# AIWAC-TF_CARD-V02.net
KiCad netlist of a schematic drawn in Altium Designer
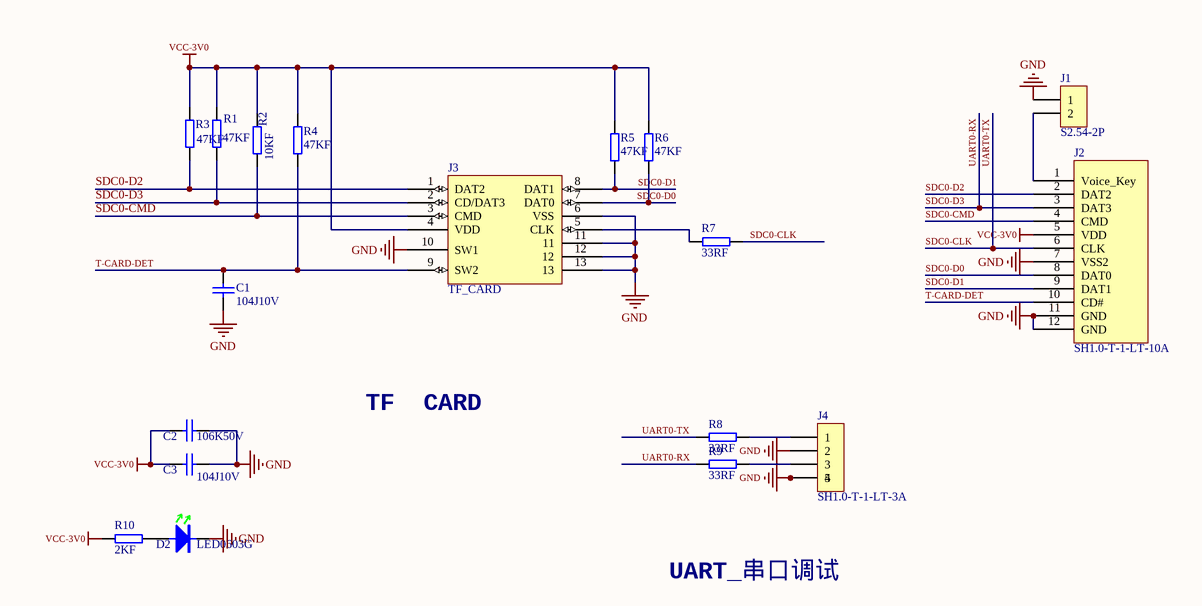
[diagram p0: AIWAC-TF_CARD-V02.SchDoc]

(export (version "E")
  (design (tool "Eeschema 10.0.6"))
  (components
    (comp (ref "C1")
      (value "104J10V")
      (footprint "C0402")
      (description "贴片电容-陶瓷")
      (libsource (lib "Capacitor") (part "C0402X7R-104J10V"))
    )
    (comp (ref "C2")
      (value "106K50V")
      (footprint "C0603")
      (description "贴片电容-陶瓷")
      (libsource (lib "Capacitor") (part "C0603X7R-106K50V"))
    )
    (comp (ref "C3")
      (value "104J10V")
      (footprint "C0402")
      (description "贴片电容-陶瓷")
      (libsource (lib "Capacitor") (part "C0402X7R-104J10V"))
    )
    (comp (ref "D2")
      (value "LED0603G")
      (footprint "D-LED0603G")
      (description "贴片二极管-LED")
      (libsource (lib "Diode") (part "DLED-0603-G"))
    )
    (comp (ref "J1")
      (value "S2.54-2P")
      (footprint "S2.54-2P")
      (description "单排排针-直针")
      (libsource (lib "Connector") (part "J-S2.54-2P"))
    )
    (comp (ref "J2")
      (value "SH1.0-T-1-LT-10A")
      (footprint "J-SH1.0-T-1-LT-10A")
      (description "接插件SH1.0-T-1-LT-10A")
      (libsource (lib "Connector") (part "SH1.0-T-1-LT-10A"))
    )
    (comp (ref "J3")
      (value "TF_CARD")
      (footprint "SD_CARD_7")
      (description "MS110-C10B-C16")
      (libsource (lib "Connector") (part "TF_CARD"))
    )
    (comp (ref "J4")
      (value "SH1.0-T-1-LT-3A")
      (footprint "J-SH1.0-T-1-LT-3A")
      (description "接插件-SH1.0-T-1-LT-3A")
      (libsource (lib "Connector") (part "SH1.0-T-1-LT-3A"))
    )
    (comp (ref "R1")
      (value "47KF")
      (footprint "R0603")
      (description "贴片电阻-通用")
      (libsource (lib "Resistor") (part "R0603-47KF"))
    )
    (comp (ref "R2")
      (value "10KF")
      (footprint "R0603")
      (description "贴片电阻-通用")
      (libsource (lib "Resistor") (part "R0603-10KF"))
    )
    (comp (ref "R3")
      (value "47KF")
      (footprint "R0603")
      (description "贴片电阻-通用")
      (libsource (lib "Resistor") (part "R0603-47KF"))
    )
    (comp (ref "R4")
      (value "47KF")
      (footprint "R0603")
      (description "贴片电阻-通用")
      (libsource (lib "Resistor") (part "R0603-47KF"))
    )
    (comp (ref "R5")
      (value "47KF")
      (footprint "R0603")
      (description "贴片电阻-通用")
      (libsource (lib "Resistor") (part "R0603-47KF"))
    )
    (comp (ref "R6")
      (value "47KF")
      (footprint "R0603")
      (description "贴片电阻-通用")
      (libsource (lib "Resistor") (part "R0603-47KF"))
    )
    (comp (ref "R7")
      (value "33RF")
      (footprint "R0603")
      (description "贴片电阻-通用")
      (libsource (lib "Resistor") (part "R0603-33RF"))
    )
    (comp (ref "R8")
      (value "33RF")
      (footprint "R0603")
      (description "贴片电阻-通用")
      (libsource (lib "Resistor") (part "R0603-33RF"))
    )
    (comp (ref "R9")
      (value "33RF")
      (footprint "R0603")
      (description "贴片电阻-通用")
      (libsource (lib "Resistor") (part "R0603-33RF"))
    )
    (comp (ref "R10")
      (value "2KF")
      (footprint "R0603")
      (description "贴片电阻-通用")
      (libsource (lib "Resistor") (part "R0603-2KF"))
    )
  )
  (nets
    (net (code "1") (name "/SDC0-CLK") (class "Default")
      (node (ref "J2") (pin "6") (pinfunction "CLK_6") (pintype "passive"))
      (node (ref "R7") (pin "1") (pinfunction "1_1") (pintype "passive"))
      (node (ref "R8") (pin "1") (pinfunction "1_1") (pintype "passive"))
    )
    (net (code "2") (name "/SDC0-CMD") (class "Default")
      (node (ref "J2") (pin "4") (pinfunction "CMD_4") (pintype "power_in"))
      (node (ref "J3") (pin "3") (pinfunction "CMD_3") (pintype "bidirectional"))
      (node (ref "R2") (pin "1") (pinfunction "1_1") (pintype "passive"))
    )
    (net (code "3") (name "/SDC0-D0") (class "Default")
      (node (ref "J2") (pin "8") (pinfunction "DAT0_8") (pintype "passive"))
      (node (ref "J3") (pin "7") (pinfunction "DAT0_7") (pintype "bidirectional"))
      (node (ref "R6") (pin "1") (pinfunction "1_1") (pintype "passive"))
    )
    (net (code "4") (name "/SDC0-D1") (class "Default")
      (node (ref "J2") (pin "9") (pinfunction "DAT1_9") (pintype "passive"))
      (node (ref "J3") (pin "8") (pinfunction "DAT1_8") (pintype "bidirectional"))
      (node (ref "R5") (pin "1") (pinfunction "1_1") (pintype "passive"))
    )
    (net (code "5") (name "/SDC0-D2") (class "Default")
      (node (ref "J2") (pin "2") (pinfunction "DAT2_2") (pintype "power_in"))
      (node (ref "J3") (pin "1") (pinfunction "DAT2_1") (pintype "bidirectional"))
      (node (ref "R3") (pin "1") (pinfunction "1_1") (pintype "passive"))
    )
    (net (code "6") (name "/SDC0-D3") (class "Default")
      (node (ref "J2") (pin "3") (pinfunction "DAT3_3") (pintype "power_in"))
      (node (ref "J3") (pin "2") (pinfunction "CD/DAT3_2") (pintype "bidirectional"))
      (node (ref "R1") (pin "1") (pinfunction "1_1") (pintype "passive"))
      (node (ref "R9") (pin "1") (pinfunction "1_1") (pintype "passive"))
    )
    (net (code "7") (name "/T-CARD-DET") (class "Default")
      (node (ref "C1") (pin "1") (pinfunction "1_1") (pintype "passive"))
      (node (ref "J2") (pin "10") (pinfunction "CD#_10") (pintype "passive"))
      (node (ref "J3") (pin "9") (pinfunction "SW2_9") (pintype "bidirectional"))
      (node (ref "R4") (pin "1") (pinfunction "1_1") (pintype "passive"))
    )
    (net (code "8") (name "GND") (class "Default")
      (node (ref "C1") (pin "2") (pinfunction "2_2") (pintype "passive"))
      (node (ref "C2") (pin "1") (pinfunction "1_1") (pintype "passive"))
      (node (ref "C3") (pin "1") (pinfunction "1_1") (pintype "passive"))
      (node (ref "D2") (pin "2") (pinfunction "2_2") (pintype "passive"))
      (node (ref "J1") (pin "1") (pinfunction "1_1") (pintype "passive"))
      (node (ref "J2") (pin "11") (pinfunction "GND_11") (pintype "passive"))
      (node (ref "J2") (pin "12") (pinfunction "GND_12") (pintype "passive"))
      (node (ref "J2") (pin "7") (pinfunction "VSS2_7") (pintype "passive"))
      (node (ref "J3") (pin "10") (pinfunction "SW1_10") (pintype "passive"))
      (node (ref "J3") (pin "11") (pinfunction "11_11") (pintype "passive"))
      (node (ref "J3") (pin "12") (pinfunction "12_12") (pintype "passive"))
      (node (ref "J3") (pin "13") (pinfunction "13_13") (pintype "passive"))
      (node (ref "J3") (pin "6") (pinfunction "VSS_6") (pintype "passive"))
      (node (ref "J4") (pin "2") (pinfunction "2_2") (pintype "passive"))
      (node (ref "J4") (pin "4") (pinfunction "4_4") (pintype "passive"))
      (node (ref "J4") (pin "5") (pinfunction "5_5") (pintype "passive"))
    )
    (net (code "9") (name "Net-(D2-Pad1)") (class "Default")
      (node (ref "D2") (pin "1") (pinfunction "1_1") (pintype "passive"))
      (node (ref "R10") (pin "2") (pinfunction "2_2") (pintype "passive"))
    )
    (net (code "10") (name "Net-(J2-Voice_Key)") (class "Default")
      (node (ref "J1") (pin "2") (pinfunction "2_2") (pintype "passive"))
      (node (ref "J2") (pin "1") (pinfunction "Voice_Key_1") (pintype "passive"))
    )
    (net (code "11") (name "Net-(J3-CLK)") (class "Default")
      (node (ref "J3") (pin "5") (pinfunction "CLK_5") (pintype "bidirectional"))
      (node (ref "R7") (pin "2") (pinfunction "2_2") (pintype "passive"))
    )
    (net (code "12") (name "Net-(J4-Pad1)") (class "Default")
      (node (ref "J4") (pin "1") (pinfunction "1_1") (pintype "passive"))
      (node (ref "R8") (pin "2") (pinfunction "2_2") (pintype "passive"))
    )
    (net (code "13") (name "Net-(J4-Pad3)") (class "Default")
      (node (ref "J4") (pin "3") (pinfunction "3_3") (pintype "passive"))
      (node (ref "R9") (pin "2") (pinfunction "2_2") (pintype "passive"))
    )
    (net (code "14") (name "VCC-3V0") (class "Default")
      (node (ref "C2") (pin "2") (pinfunction "2_2") (pintype "passive"))
      (node (ref "C3") (pin "2") (pinfunction "2_2") (pintype "passive"))
      (node (ref "J2") (pin "5") (pinfunction "VDD_5") (pintype "passive"))
      (node (ref "J3") (pin "4") (pinfunction "VDD_4") (pintype "power_in"))
      (node (ref "R1") (pin "2") (pinfunction "2_2") (pintype "passive"))
      (node (ref "R10") (pin "1") (pinfunction "1_1") (pintype "passive"))
      (node (ref "R2") (pin "2") (pinfunction "2_2") (pintype "passive"))
      (node (ref "R3") (pin "2") (pinfunction "2_2") (pintype "passive"))
      (node (ref "R4") (pin "2") (pinfunction "2_2") (pintype "passive"))
      (node (ref "R5") (pin "2") (pinfunction "2_2") (pintype "passive"))
      (node (ref "R6") (pin "2") (pinfunction "2_2") (pintype "passive"))
    )
  )
)
